# MainBoard.net
KiCad netlist of a schematic drawn in Altium Designer
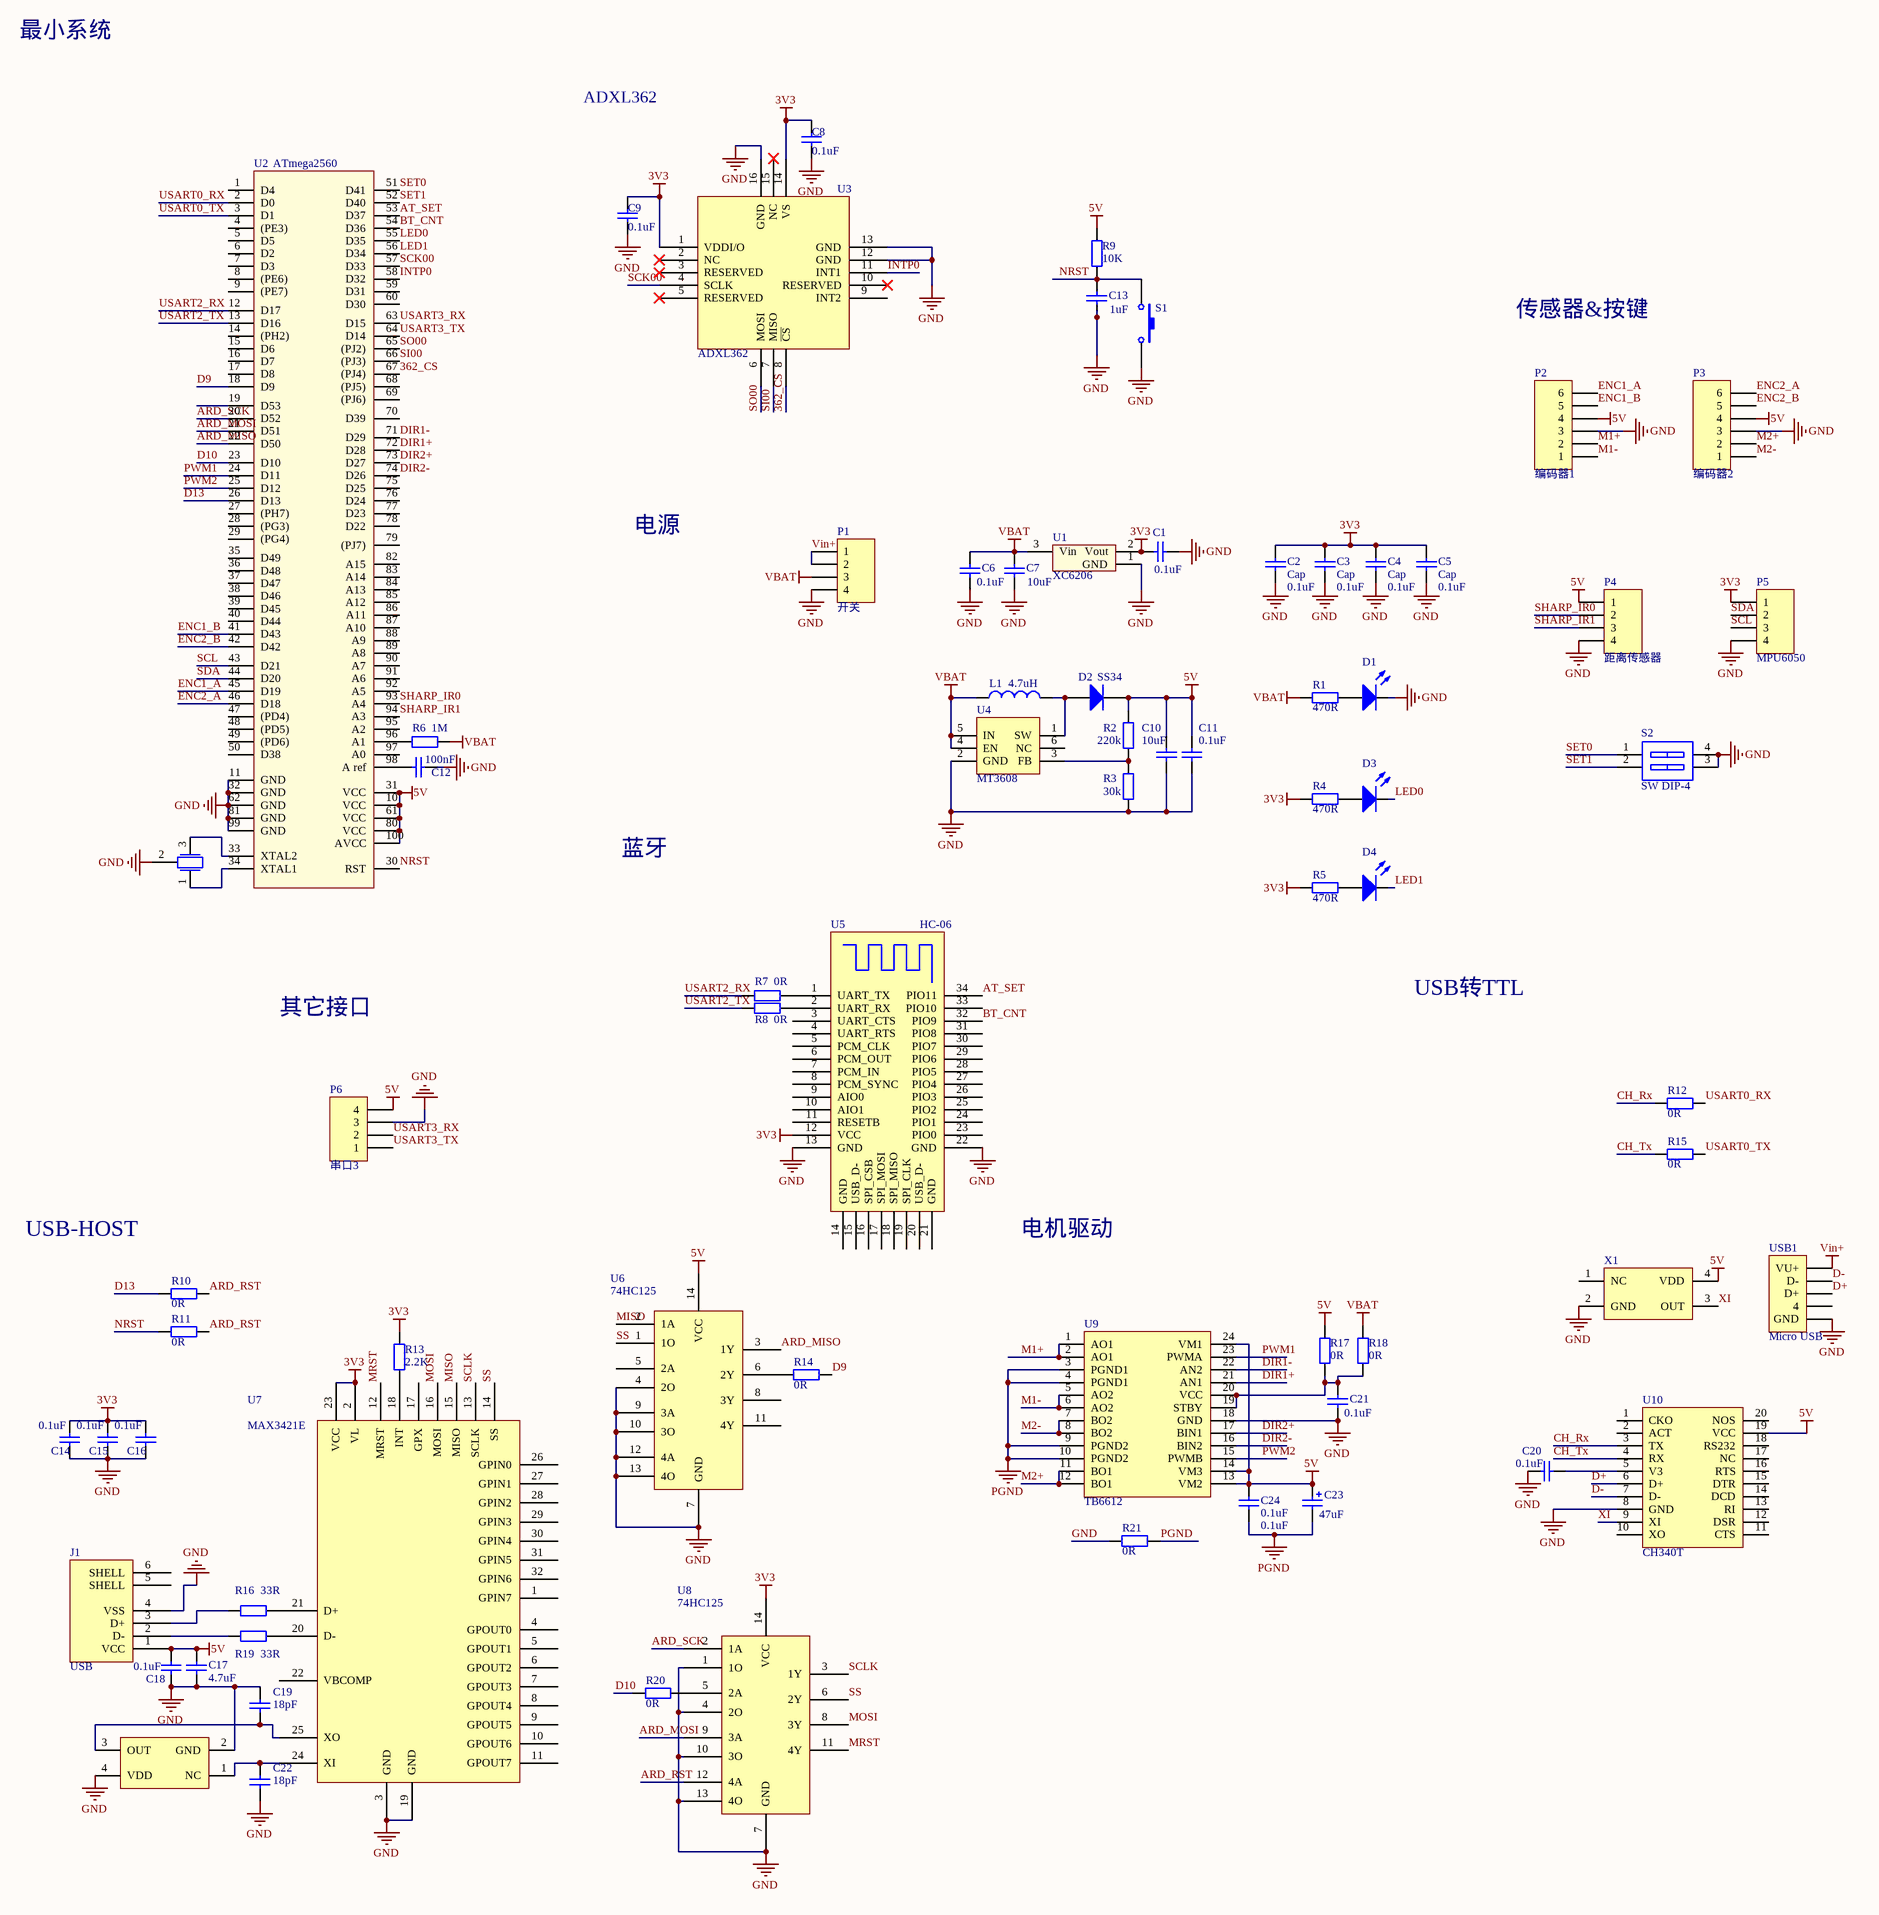
[diagram p0: MainBoard.SchDoc]

(export (version "E")
  (design (tool "Eeschema 10.0.6"))
  (components
    (comp (ref "*1") (value "5032晶振") (footprint "5032晶振") (libsource (lib "") (part "5032晶振_1")))
    (comp (ref "C1")
      (value "0.1uF")
      (footprint "0402C")
      (description "Capacitor")
      (fields (field (name "Comment") "Cap") (field (name "PUBLISHER") "Altium Limited"))
      (libsource (lib "myLib") (part "Cap"))
    )
    (comp (ref "C2")
      (value "Cap")
      (footprint "0402C")
      (description "Capacitor")
      (fields (field (name "ALTIUM_VALUE") "0.1uF") (field (name "PUBLISHER") "Altium Limited"))
      (libsource (lib "myLib") (part "Cap"))
    )
    (comp (ref "C3")
      (value "Cap")
      (footprint "0402C")
      (description "Capacitor")
      (fields (field (name "ALTIUM_VALUE") "0.1uF") (field (name "PUBLISHER") "Altium Limited"))
      (libsource (lib "myLib") (part "Cap"))
    )
    (comp (ref "C4")
      (value "Cap")
      (footprint "0402C")
      (description "Capacitor")
      (fields (field (name "ALTIUM_VALUE") "0.1uF") (field (name "PUBLISHER") "Altium Limited"))
      (libsource (lib "myLib") (part "Cap"))
    )
    (comp (ref "C5")
      (value "Cap")
      (footprint "0402C")
      (description "Capacitor")
      (fields (field (name "ALTIUM_VALUE") "0.1uF") (field (name "PUBLISHER") "Altium Limited"))
      (libsource (lib "myLib") (part "Cap"))
    )
    (comp (ref "C6")
      (value "0.1uF")
      (footprint "0402C")
      (description "Capacitor")
      (fields (field (name "Comment") "Cap") (field (name "PUBLISHER") "Altium Limited"))
      (libsource (lib "myLib") (part "Cap"))
    )
    (comp (ref "C7")
      (value "10uF")
      (footprint "0603_M")
      (description "Capacitor")
      (fields (field (name "Comment") "Cap") (field (name "PUBLISHER") "Altium Limited"))
      (libsource (lib "myLib") (part "Cap"))
    )
    (comp (ref "C8")
      (value "0.1uF")
      (footprint "0805")
      (description "Capacitor 0805")
      (fields (field (name "PUBLISHER") "Altium Limited"))
      (libsource (lib "MAE1_Integrated_Library_Ver1.05_20131010") (part "Cap2"))
    )
    (comp (ref "C9")
      (value "0.1uF")
      (footprint "0805")
      (description "Capacitor 0805")
      (fields (field (name "PUBLISHER") "Altium Limited"))
      (libsource (lib "MAE1_Integrated_Library_Ver1.05_20131010") (part "Cap2"))
    )
    (comp (ref "C10")
      (value "10uF")
      (footprint "0603_M")
      (description "Capacitor 100nF (104) ±10% 25V 0603")
      (fields (field (name "PUBLISHER") "Altium Limited"))
      (libsource (lib "Miscellaneous Devices") (part "Cap"))
    )
    (comp (ref "C11")
      (value "0.1uF")
      (footprint "0402C")
      (description "Capacitor (Semiconductor SIM Model)")
      (fields (field (name "PUBLISHER") "Altium Limited"))
      (libsource (lib "Miscellaneous Devices") (part "Cap Semi"))
    )
    (comp (ref "C12")
      (value "100nF")
      (footprint "0402")
      (description "Capacitor")
      (fields (field (name "Comment") "电容_0402") (field (name "PUBLISHER") "Altium Limited"))
      (libsource (lib "myLib") (part "电容_0402"))
    )
    (comp (ref "C13")
      (value "1uF")
      (footprint "0402C")
      (description "Capacitor")
      (fields (field (name "Comment") "Cap") (field (name "PUBLISHER") "Altium Limited"))
      (libsource (lib "myLib") (part "Cap"))
    )
    (comp (ref "C14")
      (value "0.1uF")
      (footprint "0402")
      (description "Capacitor")
      (fields (field (name "Comment") "电容_0603") (field (name "PUBLISHER") "Altium Limited"))
      (libsource (lib "myLib") (part "电容_0603"))
    )
    (comp (ref "C15")
      (value "0.1uF")
      (footprint "0402")
      (description "Capacitor")
      (fields (field (name "Comment") "电容_0603") (field (name "PUBLISHER") "Altium Limited"))
      (libsource (lib "myLib") (part "电容_0603"))
    )
    (comp (ref "C16")
      (value "0.1uF")
      (footprint "0402")
      (description "Capacitor")
      (fields (field (name "Comment") "电容_0603") (field (name "PUBLISHER") "Altium Limited"))
      (libsource (lib "myLib") (part "电容_0603"))
    )
    (comp (ref "C17")
      (value "4.7uF")
      (footprint "C1206")
      (description "Capacitor (Semiconductor SIM Model)")
      (fields (field (name "Comment") "Cap Semi") (field (name "PUBLISHER") "Altium Limited"))
      (libsource (lib "Miscellaneous Devices") (part "Cap Semi"))
    )
    (comp (ref "C18")
      (value "0.1uF")
      (footprint "0402")
      (description "Capacitor")
      (fields (field (name "Comment") "电容_0603") (field (name "PUBLISHER") "Altium Limited"))
      (libsource (lib "myLib") (part "电容_0603"))
    )
    (comp (ref "C19")
      (value "18pF")
      (footprint "0402")
      (description "Capacitor")
      (fields (field (name "Comment") "电容_0603") (field (name "PUBLISHER") "Altium Limited"))
      (libsource (lib "myLib") (part "电容_0603"))
    )
    (comp (ref "C20")
      (value "0.1uF")
      (footprint "0402C")
      (description "Capacitor")
      (fields (field (name "Comment") "Cap") (field (name "PUBLISHER") "Altium Limited"))
      (libsource (lib "myLib") (part "Cap"))
    )
    (comp (ref "C21")
      (value "0.1uF")
      (footprint "0603_M")
      (description "Capacitor")
      (fields (field (name "Comment") "value") (field (name "PUBLISHER") "Altium Limited"))
      (libsource (lib "Miscellaneous Devices") (part "Cap"))
    )
    (comp (ref "C22")
      (value "18pF")
      (footprint "0402")
      (description "Capacitor")
      (fields (field (name "Comment") "电容_0603") (field (name "PUBLISHER") "Altium Limited"))
      (libsource (lib "myLib") (part "电容_0603"))
    )
    (comp (ref "C23")
      (value "47uF")
      (footprint "CAP 6X7mm 贴片电解")
      (description "Polarized Capacitor (Radial)")
      (fields (field (name "Comment") "钽电容6x7mm") (field (name "PUBLISHER") "Altium Limited"))
      (libsource (lib "myLib") (part "钽电容6x7mm"))
    )
    (comp (ref "C24")
      (value "0.1uF")
      (footprint "0603_M")
      (description "Capacitor")
      (fields (field (name "ALTIUM_VALUE") "0.1uF") (field (name "PUBLISHER") "Altium Limited"))
      (libsource (lib "Miscellaneous Devices") (part "Cap"))
    )
    (comp (ref "D1")
      (value "LED")
      (footprint "0603_M")
      (description "Typical INFRARED GaAs LED")
      (fields (field (name "PUBLISHER") "Altium Limited"))
      (libsource (lib "myLib") (part "LED0"))
    )
    (comp (ref "D2")
      (value "SS34")
      (footprint "DO-214")
      (description "Diode  SS34 DO214-AC")
      (fields (field (name "PUBLISHER") "Altium Limited"))
      (libsource (lib "Miscellaneous Devices") (part "Diode"))
    )
    (comp (ref "D3")
      (value "LED")
      (footprint "0603_M")
      (description "Typical INFRARED GaAs LED")
      (fields (field (name "PUBLISHER") "Altium Limited"))
      (libsource (lib "myLib") (part "LED0"))
    )
    (comp (ref "D4")
      (value "LED")
      (footprint "0603_M")
      (description "Typical INFRARED GaAs LED")
      (fields (field (name "PUBLISHER") "Altium Limited"))
      (libsource (lib "myLib") (part "LED0"))
    )
    (comp (ref "J1")
      (value "USB")
      (footprint "USB_A1")
      (description "USB接口")
      (libsource (lib "myLib") (part "USB"))
    )
    (comp (ref "L1")
      (value "4.7uH")
      (footprint "贴片电感CD32")
      (description "Inductor, 6.8uH, 4.5A, 1054 SMD")
      (fields (field (name "PUBLISHER") "Altium Limited"))
      (libsource (lib "myLib") (part "贴片电感"))
    )
    (comp (ref "P1")
      (value "开关")
      (footprint "HDR1X4")
      (description "Header, 4-Pin")
      (fields (field (name "PUBLISHER") "Altium Limited"))
      (libsource (lib "Miscellaneous Connectors") (part "Header 4"))
    )
    (comp (ref "P2")
      (value "编码器1")
      (footprint "接插件6x1.25mm")
      (libsource (lib "myLib") (part "接插件6x1.25mm_1"))
    )
    (comp (ref "P3")
      (value "编码器2")
      (footprint "接插件6x1.25mm")
      (libsource (lib "myLib") (part "接插件6x1.25mm_1"))
    )
    (comp (ref "P4")
      (value "距离传感器")
      (footprint "接插件4x1.25mm")
      (description "Header, 4-Pin")
      (fields (field (name "PUBLISHER") "Altium Limited"))
      (libsource (lib "Miscellaneous Connectors") (part "MHDR1X4"))
    )
    (comp (ref "P5") (value "MPU6050") (footprint "接插件4x1.25mm") (libsource (lib "") (part "接插件4x1.25mm_1")))
    (comp (ref "P6") (value "串口3") (footprint "接插件4x1.25mm") (libsource (lib "myLib") (part "接插件4x1.25mm")))
    (comp (ref "R1")
      (value "470R")
      (footprint "0402C")
      (description "Resistor")
      (fields (field (name "Comment") "电阻_0402") (field (name "PUBLISHER") "Altium Limited"))
      (libsource (lib "myLib") (part "电阻_0402"))
    )
    (comp (ref "R2")
      (value "220k")
      (footprint "0603_M")
      (description "Resistor, 22R 1% 0603 (1608)")
      (fields (field (name "PUBLISHER") "Altium Limited"))
      (libsource (lib "Miscellaneous Devices") (part "Res2"))
    )
    (comp (ref "R3")
      (value "30k")
      (footprint "0603_M")
      (description "Resistor, 22R 1% 0603 (1608)")
      (fields (field (name "PUBLISHER") "Altium Limited"))
      (libsource (lib "Miscellaneous Devices") (part "Res2"))
    )
    (comp (ref "R4")
      (value "470R")
      (footprint "0402C")
      (description "Resistor")
      (fields (field (name "Comment") "电阻_0402") (field (name "PUBLISHER") "Altium Limited"))
      (libsource (lib "myLib") (part "电阻_0402"))
    )
    (comp (ref "R5")
      (value "470R")
      (footprint "0402C")
      (description "Resistor")
      (fields (field (name "Comment") "电阻_0402") (field (name "PUBLISHER") "Altium Limited"))
      (libsource (lib "myLib") (part "电阻_0402"))
    )
    (comp (ref "R6")
      (value "1M")
      (footprint "0402C")
      (description "Resistor")
      (fields (field (name "Comment") "电阻_0402") (field (name "PUBLISHER") "Altium Limited"))
      (libsource (lib "myLib") (part "电阻_0402"))
    )
    (comp (ref "R7")
      (value "0R")
      (footprint "0R电阻")
      (description "Resistor")
      (fields (field (name "Comment") "0R电阻") (field (name "PUBLISHER") "Altium Limited"))
      (libsource (lib "myLib") (part "0R电阻"))
    )
    (comp (ref "R8")
      (value "0R")
      (footprint "0R电阻")
      (description "Resistor")
      (fields (field (name "Comment") "0R电阻") (field (name "PUBLISHER") "Altium Limited"))
      (libsource (lib "myLib") (part "0R电阻"))
    )
    (comp (ref "R9")
      (value "10K")
      (footprint "0402C")
      (description "Resistor")
      (fields (field (name "Comment") "Res2") (field (name "PUBLISHER") "Altium Limited"))
      (libsource (lib "myLib") (part "Res2"))
    )
    (comp (ref "R10")
      (value "0R")
      (footprint "0R电阻")
      (description "Resistor")
      (fields (field (name "Comment") "0R电阻") (field (name "PUBLISHER") "Altium Limited"))
      (libsource (lib "myLib") (part "0R电阻"))
    )
    (comp (ref "R11")
      (value "0R")
      (footprint "0R电阻")
      (description "Resistor")
      (fields (field (name "Comment") "0R电阻") (field (name "PUBLISHER") "Altium Limited"))
      (libsource (lib "myLib") (part "0R电阻"))
    )
    (comp (ref "R12")
      (value "0R")
      (footprint "0R电阻")
      (description "Resistor")
      (fields (field (name "Comment") "0R电阻") (field (name "PUBLISHER") "Altium Limited"))
      (libsource (lib "myLib") (part "0R电阻"))
    )
    (comp (ref "R13")
      (value "2.2K")
      (footprint "0603_M")
      (description "Resistor")
      (fields (field (name "Comment") "电阻_0603") (field (name "PUBLISHER") "Altium Limited"))
      (libsource (lib "") (part "电阻_0603_1"))
    )
    (comp (ref "R14")
      (value "0R")
      (footprint "0R电阻")
      (description "Resistor")
      (fields (field (name "Comment") "0R电阻") (field (name "PUBLISHER") "Altium Limited"))
      (libsource (lib "myLib") (part "0R电阻"))
    )
    (comp (ref "R15")
      (value "0R")
      (footprint "0R电阻")
      (description "Resistor")
      (fields (field (name "Comment") "0R电阻") (field (name "PUBLISHER") "Altium Limited"))
      (libsource (lib "myLib") (part "0R电阻"))
    )
    (comp (ref "R16")
      (value "33R")
      (footprint "0603_M")
      (description "Resistor")
      (fields (field (name "Comment") "电阻_0603") (field (name "PUBLISHER") "Altium Limited"))
      (libsource (lib "myLib") (part "电阻_0603"))
    )
    (comp (ref "R17")
      (value "0R")
      (footprint "0R电阻")
      (description "Resistor")
      (fields (field (name "Comment") "0R电阻") (field (name "PUBLISHER") "Altium Limited"))
      (libsource (lib "") (part "0R电阻_1"))
    )
    (comp (ref "R18")
      (value "0R")
      (footprint "0R电阻")
      (description "Resistor")
      (fields (field (name "Comment") "0R电阻") (field (name "PUBLISHER") "Altium Limited"))
      (libsource (lib "") (part "0R电阻_1"))
    )
    (comp (ref "R19")
      (value "33R")
      (footprint "0603_M")
      (description "Resistor")
      (fields (field (name "Comment") "电阻_0603") (field (name "PUBLISHER") "Altium Limited"))
      (libsource (lib "myLib") (part "电阻_0603"))
    )
    (comp (ref "R20")
      (value "0R")
      (footprint "0R电阻")
      (description "Resistor")
      (fields (field (name "Comment") "0R电阻") (field (name "PUBLISHER") "Altium Limited"))
      (libsource (lib "myLib") (part "0R电阻"))
    )
    (comp (ref "R21")
      (value "0R")
      (footprint "0R电阻")
      (description "Resistor")
      (fields (field (name "Comment") "0R电阻") (field (name "PUBLISHER") "Altium Limited"))
      (libsource (lib "myLib") (part "0R电阻"))
    )
    (comp (ref "S1")
      (value "SW-PB")
      (footprint "SW_PB2_A1")
      (description "微动开关")
      (fields (field (name "PUBLISHER") "Altium Limited"))
      (libsource (lib "myLib") (part "SW-PB"))
    )
    (comp (ref "S2")
      (value "SW DIP-4")
      (footprint "SW8_4BIT")
      (description "编码开关")
      (fields (field (name "PUBLISHER") "Altium Limited"))
      (libsource (lib "myLib") (part "SW DIP-4"))
    )
    (comp (ref "U1") (value "XC6206") (footprint "SOT-23") (libsource (lib "myLib") (part "XC6206")))
    (comp (ref "U2") (value "ATmega2560") (footprint "QFP-100") (libsource (lib "myLib") (part "ATmega2560")))
    (comp (ref "U3")
      (value "ADXL362")
      (footprint "脚部传感器1:MAX21100")
      (libsource (lib "pedometer") (part "ADXL362"))
    )
    (comp (ref "U4")
      (value "MT3608")
      (footprint "SOT23-6")
      (description "升压IC")
      (libsource (lib "my元器件原理图") (part "MT3608"))
    )
    (comp (ref "U5")
      (value "HC-06")
      (footprint "HM_01_02_09_10")
      (description "HM bluetooth module HM-01,HM-02,HM-09")
      (libsource (lib "HMSoft") (part "HM01_02_09_1"))
    )
    (comp (ref "U6") (value "74HC125") (footprint "SOIC-14") (libsource (lib "myLib") (part "74HC125")))
    (comp (ref "U7") (value "MAX3421E") (footprint "TQFP-32") (libsource (lib "myLib") (part "MAX3421E")))
    (comp (ref "U8") (value "74HC125") (footprint "SOIC-14") (libsource (lib "myLib") (part "74HC125")))
    (comp (ref "U9") (value "TB6612") (footprint "SOP65P760-24") (libsource (lib "Mylib") (part "TB6612")))
    (comp (ref "U10") (value "CH340T") (footprint "SSOP20") (libsource (lib "myLib") (part "CH340T")))
    (comp (ref "USB1")
      (value "Micro USB")
      (footprint "USB MICRO")
      (description "USB")
      (fields (field (name "PUBLISHER") "Altium Limited"))
      (libsource (lib "myLib") (part "Micro USB"))
    )
    (comp (ref "X1") (value "5032晶振") (footprint "5032晶振") (libsource (lib "myLib") (part "5032晶振")))
    (comp (ref "Y1")
      (value "XTAL-3PIN")
      (footprint "X-CPX20")
      (description "贴片晶振")
      (libsource (lib "myLib") (part "XTAL-3PIN"))
    )
  )
  (nets
    (net (code "1") (name "/362_CS") (class "Default")
      (node (ref "U2") (pin "67") (pinfunction "(PJ4)_67") (pintype "passive"))
      (node (ref "U3") (pin "8") (pinfunction "~{CS}_8") (pintype "passive"))
    )
    (net (code "2") (name "/ARD_MISO") (class "Default")
      (node (ref "U2") (pin "22") (pinfunction "D50_22") (pintype "passive"))
      (node (ref "U6") (pin "3") (pinfunction "1Y_3") (pintype "passive"))
    )
    (net (code "3") (name "/ARD_MOSI") (class "Default")
      (node (ref "U2") (pin "21") (pinfunction "D51_21") (pintype "passive"))
      (node (ref "U8") (pin "9") (pinfunction "3A_9") (pintype "passive"))
    )
    (net (code "4") (name "/ARD_RST") (class "Default")
      (node (ref "R10") (pin "2") (pinfunction "2_2") (pintype "passive"))
      (node (ref "R11") (pin "2") (pinfunction "2_2") (pintype "passive"))
      (node (ref "U8") (pin "12") (pinfunction "4A_12") (pintype "passive"))
    )
    (net (code "5") (name "/ARD_SCK") (class "Default")
      (node (ref "U2") (pin "20") (pinfunction "D52_20") (pintype "passive"))
      (node (ref "U8") (pin "2") (pinfunction "1A_2") (pintype "passive"))
    )
    (net (code "6") (name "/AT_SET") (class "Default")
      (node (ref "U2") (pin "53") (pinfunction "D37_53") (pintype "passive"))
      (node (ref "U5") (pin "34") (pinfunction "PIO11_34") (pintype "passive"))
    )
    (net (code "7") (name "/BT_CNT") (class "Default")
      (node (ref "U2") (pin "54") (pinfunction "D36_54") (pintype "passive"))
      (node (ref "U5") (pin "32") (pinfunction "PIO9_32") (pintype "passive"))
    )
    (net (code "8") (name "/CH_Rx") (class "Default")
      (node (ref "R12") (pin "1") (pinfunction "1_1") (pintype "passive"))
      (node (ref "U10") (pin "3") (pinfunction "TX_3") (pintype "passive"))
    )
    (net (code "9") (name "/CH_Tx") (class "Default")
      (node (ref "R15") (pin "1") (pinfunction "1_1") (pintype "passive"))
      (node (ref "U10") (pin "4") (pinfunction "RX_4") (pintype "passive"))
    )
    (net (code "10") (name "/D+") (class "Default")
      (node (ref "U10") (pin "6") (pinfunction "D+_6") (pintype "passive"))
      (node (ref "USB1") (pin "3") (pinfunction "D+_3") (pintype "passive"))
    )
    (net (code "11") (name "/D-") (class "Default")
      (node (ref "U10") (pin "7") (pinfunction "D-_7") (pintype "passive"))
      (node (ref "USB1") (pin "2") (pinfunction "D-_2") (pintype "passive"))
    )
    (net (code "12") (name "/D9") (class "Default")
      (node (ref "R14") (pin "2") (pinfunction "2_2") (pintype "passive"))
      (node (ref "U2") (pin "18") (pinfunction "D9_18") (pintype "passive"))
    )
    (net (code "13") (name "/D10") (class "Default")
      (node (ref "R20") (pin "1") (pinfunction "1_1") (pintype "passive"))
      (node (ref "U2") (pin "23") (pinfunction "D10_23") (pintype "passive"))
    )
    (net (code "14") (name "/D13") (class "Default")
      (node (ref "R10") (pin "1") (pinfunction "1_1") (pintype "passive"))
      (node (ref "U2") (pin "26") (pinfunction "D13_26") (pintype "passive"))
    )
    (net (code "15") (name "/DIR1+") (class "Default")
      (node (ref "U2") (pin "72") (pinfunction "D28_72") (pintype "passive"))
      (node (ref "U9") (pin "21") (pinfunction "AN1_21") (pintype "passive"))
    )
    (net (code "16") (name "/DIR1-") (class "Default")
      (node (ref "U2") (pin "71") (pinfunction "D29_71") (pintype "passive"))
      (node (ref "U9") (pin "22") (pinfunction "AN2_22") (pintype "passive"))
    )
    (net (code "17") (name "/DIR2+") (class "Default")
      (node (ref "U2") (pin "73") (pinfunction "D27_73") (pintype "passive"))
      (node (ref "U9") (pin "17") (pinfunction "BIN1_17") (pintype "passive"))
    )
    (net (code "18") (name "/DIR2-") (class "Default")
      (node (ref "U2") (pin "74") (pinfunction "D26_74") (pintype "passive"))
      (node (ref "U9") (pin "16") (pinfunction "BIN2_16") (pintype "passive"))
    )
    (net (code "19") (name "/ENC1_A") (class "Default")
      (node (ref "P2") (pin "6") (pinfunction "6_6") (pintype "passive"))
      (node (ref "U2") (pin "45") (pinfunction "D19_45") (pintype "passive"))
    )
    (net (code "20") (name "/ENC1_B") (class "Default")
      (node (ref "P2") (pin "5") (pinfunction "5_5") (pintype "passive"))
      (node (ref "U2") (pin "41") (pinfunction "D43_41") (pintype "passive"))
    )
    (net (code "21") (name "/ENC2_A") (class "Default")
      (node (ref "P3") (pin "6") (pinfunction "6_6") (pintype "passive"))
      (node (ref "U2") (pin "46") (pinfunction "D18_46") (pintype "passive"))
    )
    (net (code "22") (name "/ENC2_B") (class "Default")
      (node (ref "P3") (pin "5") (pinfunction "5_5") (pintype "passive"))
      (node (ref "U2") (pin "42") (pinfunction "D42_42") (pintype "passive"))
    )
    (net (code "23") (name "/INTP0") (class "Default")
      (node (ref "U2") (pin "58") (pinfunction "D32_58") (pintype "passive"))
      (node (ref "U3") (pin "11") (pinfunction "INT1_11") (pintype "passive"))
    )
    (net (code "24") (name "/LED0") (class "Default")
      (node (ref "D3") (pin "2") (pinfunction "K_2") (pintype "passive"))
      (node (ref "U2") (pin "55") (pinfunction "D35_55") (pintype "passive"))
    )
    (net (code "25") (name "/LED1") (class "Default")
      (node (ref "D4") (pin "2") (pinfunction "K_2") (pintype "passive"))
      (node (ref "U2") (pin "56") (pinfunction "D34_56") (pintype "passive"))
    )
    (net (code "26") (name "/M1+") (class "Default")
      (node (ref "P2") (pin "2") (pinfunction "2_2") (pintype "passive"))
      (node (ref "U9") (pin "1") (pinfunction "AO1_1") (pintype "passive"))
      (node (ref "U9") (pin "2") (pinfunction "AO1_2") (pintype "passive"))
    )
    (net (code "27") (name "/M1-") (class "Default")
      (node (ref "P2") (pin "1") (pinfunction "1_1") (pintype "passive"))
      (node (ref "U9") (pin "5") (pinfunction "AO2_5") (pintype "passive"))
      (node (ref "U9") (pin "6") (pinfunction "AO2_6") (pintype "passive"))
    )
    (net (code "28") (name "/M2+") (class "Default")
      (node (ref "P3") (pin "2") (pinfunction "2_2") (pintype "passive"))
      (node (ref "U9") (pin "11") (pinfunction "BO1_11") (pintype "passive"))
      (node (ref "U9") (pin "12") (pinfunction "BO1_12") (pintype "passive"))
    )
    (net (code "29") (name "/M2-") (class "Default")
      (node (ref "P3") (pin "1") (pinfunction "1_1") (pintype "passive"))
      (node (ref "U9") (pin "7") (pinfunction "BO2_7") (pintype "passive"))
      (node (ref "U9") (pin "8") (pinfunction "BO2_8") (pintype "passive"))
    )
    (net (code "30") (name "/MISO") (class "Default")
      (node (ref "U6") (pin "2") (pinfunction "1A_2") (pintype "passive"))
      (node (ref "U7") (pin "15") (pinfunction "MISO_15") (pintype "passive"))
    )
    (net (code "31") (name "/MOSI") (class "Default")
      (node (ref "U7") (pin "16") (pinfunction "MOSI_16") (pintype "passive"))
      (node (ref "U8") (pin "8") (pinfunction "3Y_8") (pintype "passive"))
    )
    (net (code "32") (name "/MRST") (class "Default")
      (node (ref "U7") (pin "12") (pinfunction "MRST_12") (pintype "passive"))
      (node (ref "U8") (pin "11") (pinfunction "4Y_11") (pintype "passive"))
    )
    (net (code "33") (name "/NRST") (class "Default")
      (node (ref "C13") (pin "2") (pinfunction "2_2") (pintype "passive"))
      (node (ref "R11") (pin "1") (pinfunction "1_1") (pintype "passive"))
      (node (ref "R9") (pin "1") (pinfunction "1_1") (pintype "passive"))
      (node (ref "S1") (pin "1") (pinfunction "1_1") (pintype "passive"))
      (node (ref "U2") (pin "30") (pinfunction "RST_30") (pintype "passive"))
    )
    (net (code "34") (name "/PWM1") (class "Default")
      (node (ref "U2") (pin "24") (pinfunction "D11_24") (pintype "passive"))
      (node (ref "U9") (pin "23") (pinfunction "PWMA_23") (pintype "passive"))
    )
    (net (code "35") (name "/PWM2") (class "Default")
      (node (ref "U2") (pin "25") (pinfunction "D12_25") (pintype "passive"))
      (node (ref "U9") (pin "15") (pinfunction "PWMB_15") (pintype "passive"))
    )
    (net (code "36") (name "/SCK00") (class "Default")
      (node (ref "U2") (pin "57") (pinfunction "D33_57") (pintype "passive"))
      (node (ref "U3") (pin "4") (pinfunction "SCLK_4") (pintype "passive"))
    )
    (net (code "37") (name "/SCL") (class "Default")
      (node (ref "P5") (pin "3") (pinfunction "3_3") (pintype "passive"))
      (node (ref "U2") (pin "43") (pinfunction "D21_43") (pintype "passive"))
    )
    (net (code "38") (name "/SCLK") (class "Default")
      (node (ref "U7") (pin "13") (pinfunction "SCLK_13") (pintype "passive"))
      (node (ref "U8") (pin "3") (pinfunction "1Y_3") (pintype "passive"))
    )
    (net (code "39") (name "/SDA") (class "Default")
      (node (ref "P5") (pin "2") (pinfunction "2_2") (pintype "passive"))
      (node (ref "U2") (pin "44") (pinfunction "D20_44") (pintype "passive"))
    )
    (net (code "40") (name "/SET0") (class "Default")
      (node (ref "S2") (pin "1") (pinfunction "A1_1") (pintype "passive"))
      (node (ref "U2") (pin "51") (pinfunction "D41_51") (pintype "passive"))
    )
    (net (code "41") (name "/SET1") (class "Default")
      (node (ref "S2") (pin "2") (pinfunction "A2_2") (pintype "passive"))
      (node (ref "U2") (pin "52") (pinfunction "D40_52") (pintype "passive"))
    )
    (net (code "42") (name "/SHARP_IR0") (class "Default")
      (node (ref "P4") (pin "2") (pinfunction "2_2") (pintype "passive"))
      (node (ref "U2") (pin "93") (pinfunction "A4_93") (pintype "passive"))
    )
    (net (code "43") (name "/SHARP_IR1") (class "Default")
      (node (ref "P4") (pin "3") (pinfunction "3_3") (pintype "passive"))
      (node (ref "U2") (pin "94") (pinfunction "A3_94") (pintype "passive"))
    )
    (net (code "44") (name "/SI00") (class "Default")
      (node (ref "U2") (pin "66") (pinfunction "(PJ3)_66") (pintype "passive"))
      (node (ref "U3") (pin "7") (pinfunction "MISO_7") (pintype "passive"))
    )
    (net (code "45") (name "/SO00") (class "Default")
      (node (ref "U2") (pin "65") (pinfunction "(PJ2)_65") (pintype "passive"))
      (node (ref "U3") (pin "6") (pinfunction "MOSI_6") (pintype "passive"))
    )
    (net (code "46") (name "/SS") (class "Default")
      (node (ref "U6") (pin "1") (pinfunction "1O_1") (pintype "passive"))
      (node (ref "U7") (pin "14") (pinfunction "SS_14") (pintype "passive"))
      (node (ref "U8") (pin "6") (pinfunction "2Y_6") (pintype "passive"))
    )
    (net (code "47") (name "/USART0_RX") (class "Default")
      (node (ref "R12") (pin "2") (pinfunction "2_2") (pintype "passive"))
      (node (ref "U2") (pin "2") (pinfunction "D0_2") (pintype "passive"))
    )
    (net (code "48") (name "/USART0_TX") (class "Default")
      (node (ref "R15") (pin "2") (pinfunction "2_2") (pintype "passive"))
      (node (ref "U2") (pin "3") (pinfunction "D1_3") (pintype "passive"))
    )
    (net (code "49") (name "/USART2_RX") (class "Default")
      (node (ref "R7") (pin "1") (pinfunction "1_1") (pintype "passive"))
      (node (ref "U2") (pin "12") (pinfunction "D17_12") (pintype "passive"))
    )
    (net (code "50") (name "/USART2_TX") (class "Default")
      (node (ref "R8") (pin "1") (pinfunction "1_1") (pintype "passive"))
      (node (ref "U2") (pin "13") (pinfunction "D16_13") (pintype "passive"))
    )
    (net (code "51") (name "/USART3_RX") (class "Default")
      (node (ref "P6") (pin "2") (pinfunction "2_2") (pintype "passive"))
      (node (ref "U2") (pin "63") (pinfunction "D15_63") (pintype "passive"))
    )
    (net (code "52") (name "/USART3_TX") (class "Default")
      (node (ref "P6") (pin "1") (pinfunction "1_1") (pintype "passive"))
      (node (ref "U2") (pin "64") (pinfunction "D14_64") (pintype "passive"))
    )
    (net (code "53") (name "/XI") (class "Default")
      (node (ref "U10") (pin "9") (pinfunction "XI_9") (pintype "passive"))
      (node (ref "X1") (pin "3") (pinfunction "OUT_3") (pintype "passive"))
    )
    (net (code "54") (name "3V3") (class "Default")
      (node (ref "C1") (pin "1") (pinfunction "1_1") (pintype "passive"))
      (node (ref "C14") (pin "1") (pinfunction "1_1") (pintype "passive"))
      (node (ref "C15") (pin "1") (pinfunction "1_1") (pintype "passive"))
      (node (ref "C16") (pin "1") (pinfunction "1_1") (pintype "passive"))
      (node (ref "C2") (pin "2") (pinfunction "2_2") (pintype "passive"))
      (node (ref "C3") (pin "2") (pinfunction "2_2") (pintype "passive"))
      (node (ref "C4") (pin "2") (pinfunction "2_2") (pintype "passive"))
      (node (ref "C5") (pin "2") (pinfunction "2_2") (pintype "passive"))
      (node (ref "C8") (pin "2") (pinfunction "2_2") (pintype "passive"))
      (node (ref "C9") (pin "2") (pinfunction "2_2") (pintype "passive"))
      (node (ref "P5") (pin "1") (pinfunction "1_1") (pintype "passive"))
      (node (ref "R13") (pin "2") (pinfunction "2_2") (pintype "passive"))
      (node (ref "R4") (pin "1") (pinfunction "1_1") (pintype "passive"))
      (node (ref "R5") (pin "1") (pinfunction "1_1") (pintype "passive"))
      (node (ref "U1") (pin "2") (pinfunction "Vout_2") (pintype "passive"))
      (node (ref "U3") (pin "1") (pinfunction "VDDI/O_1") (pintype "passive"))
      (node (ref "U3") (pin "14") (pinfunction "VS_14") (pintype "passive"))
      (node (ref "U5") (pin "12") (pinfunction "VCC_12") (pintype "passive"))
      (node (ref "U7") (pin "2") (pinfunction "VL_2") (pintype "passive"))
      (node (ref "U7") (pin "23") (pinfunction "VCC_23") (pintype "passive"))
      (node (ref "U8") (pin "14") (pinfunction "VCC_14") (pintype "passive"))
    )
    (net (code "55") (name "5V") (class "Default")
      (node (ref "C10") (pin "2") (pinfunction "2_2") (pintype "passive"))
      (node (ref "C11") (pin "2") (pinfunction "2_2") (pintype "passive"))
      (node (ref "C17") (pin "2") (pinfunction "2_2") (pintype "passive"))
      (node (ref "C18") (pin "1") (pinfunction "1_1") (pintype "passive"))
      (node (ref "C23") (pin "1") (pinfunction "1_1") (pintype "passive"))
      (node (ref "C24") (pin "2") (pinfunction "2_2") (pintype "passive"))
      (node (ref "D2") (pin "2") (pinfunction "K_2") (pintype "passive"))
      (node (ref "J1") (pin "1") (pinfunction "VCC_1") (pintype "passive"))
      (node (ref "P2") (pin "4") (pinfunction "4_4") (pintype "passive"))
      (node (ref "P3") (pin "4") (pinfunction "4_4") (pintype "passive"))
      (node (ref "P4") (pin "1") (pinfunction "1_1") (pintype "passive"))
      (node (ref "P6") (pin "4") (pinfunction "4_4") (pintype "passive"))
      (node (ref "R17") (pin "2") (pinfunction "2_2") (pintype "passive"))
      (node (ref "R2") (pin "1") (pinfunction "1_1") (pintype "passive"))
      (node (ref "R9") (pin "2") (pinfunction "2_2") (pintype "passive"))
      (node (ref "U10") (pin "19") (pinfunction "VCC_19") (pintype "passive"))
      (node (ref "U2") (pin "10") (pinfunction "VCC_10") (pintype "passive"))
      (node (ref "U2") (pin "100") (pinfunction "AVCC_100") (pintype "passive"))
      (node (ref "U2") (pin "31") (pinfunction "VCC_31") (pintype "passive"))
      (node (ref "U2") (pin "61") (pinfunction "VCC_61") (pintype "passive"))
      (node (ref "U2") (pin "80") (pinfunction "VCC_80") (pintype "passive"))
      (node (ref "U6") (pin "14") (pinfunction "VCC_14") (pintype "passive"))
      (node (ref "U9") (pin "13") (pinfunction "VM2_13") (pintype "passive"))
      (node (ref "U9") (pin "14") (pinfunction "VM3_14") (pintype "passive"))
      (node (ref "U9") (pin "24") (pinfunction "VM1_24") (pintype "passive"))
      (node (ref "X1") (pin "4") (pinfunction "VDD_4") (pintype "passive"))
    )
    (net (code "56") (name "GND") (class "Default")
      (node (ref "*1") (pin "2") (pinfunction "GND_2") (pintype "passive"))
      (node (ref "*1") (pin "4") (pinfunction "VDD_4") (pintype "passive"))
      (node (ref "C1") (pin "2") (pinfunction "2_2") (pintype "passive"))
      (node (ref "C10") (pin "1") (pinfunction "1_1") (pintype "passive"))
      (node (ref "C11") (pin "1") (pinfunction "1_1") (pintype "passive"))
      (node (ref "C12") (pin "1") (pinfunction "1_1") (pintype "passive"))
      (node (ref "C13") (pin "1") (pinfunction "1_1") (pintype "passive"))
      (node (ref "C14") (pin "2") (pinfunction "2_2") (pintype "passive"))
      (node (ref "C15") (pin "2") (pinfunction "2_2") (pintype "passive"))
      (node (ref "C16") (pin "2") (pinfunction "2_2") (pintype "passive"))
      (node (ref "C17") (pin "1") (pinfunction "1_1") (pintype "passive"))
      (node (ref "C18") (pin "2") (pinfunction "2_2") (pintype "passive"))
      (node (ref "C19") (pin "1") (pinfunction "1_1") (pintype "passive"))
      (node (ref "C2") (pin "1") (pinfunction "1_1") (pintype "passive"))
      (node (ref "C20") (pin "1") (pinfunction "1_1") (pintype "passive"))
      (node (ref "C21") (pin "1") (pinfunction "1_1") (pintype "passive"))
      (node (ref "C22") (pin "2") (pinfunction "2_2") (pintype "passive"))
      (node (ref "C3") (pin "1") (pinfunction "1_1") (pintype "passive"))
      (node (ref "C4") (pin "1") (pinfunction "1_1") (pintype "passive"))
      (node (ref "C5") (pin "1") (pinfunction "1_1") (pintype "passive"))
      (node (ref "C6") (pin "1") (pinfunction "1_1") (pintype "passive"))
      (node (ref "C7") (pin "1") (pinfunction "1_1") (pintype "passive"))
      (node (ref "C8") (pin "1") (pinfunction "1_1") (pintype "passive"))
      (node (ref "C9") (pin "1") (pinfunction "1_1") (pintype "passive"))
      (node (ref "D1") (pin "2") (pinfunction "K_2") (pintype "passive"))
      (node (ref "J1") (pin "4") (pinfunction "VSS_4") (pintype "passive"))
      (node (ref "P1") (pin "4") (pinfunction "4_4") (pintype "passive"))
      (node (ref "P2") (pin "3") (pinfunction "3_3") (pintype "passive"))
      (node (ref "P3") (pin "3") (pinfunction "3_3") (pintype "passive"))
      (node (ref "P4") (pin "4") (pinfunction "4_4") (pintype "passive"))
      (node (ref "P5") (pin "4") (pinfunction "4_4") (pintype "passive"))
      (node (ref "P6") (pin "3") (pinfunction "3_3") (pintype "passive"))
      (node (ref "R21") (pin "1") (pinfunction "1_1") (pintype "passive"))
      (node (ref "R3") (pin "2") (pinfunction "2_2") (pintype "passive"))
      (node (ref "S1") (pin "2") (pinfunction "2_2") (pintype "passive"))
      (node (ref "S2") (pin "3") (pinfunction "B2_3") (pintype "passive"))
      (node (ref "S2") (pin "4") (pinfunction "B1_4") (pintype "passive"))
      (node (ref "U1") (pin "1") (pinfunction "GND_1") (pintype "passive"))
      (node (ref "U10") (pin "8") (pinfunction "GND_8") (pintype "passive"))
      (node (ref "U2") (pin "11") (pinfunction "GND_11") (pintype "passive"))
      (node (ref "U2") (pin "32") (pinfunction "GND_32") (pintype "passive"))
      (node (ref "U2") (pin "62") (pinfunction "GND_62") (pintype "passive"))
      (node (ref "U2") (pin "81") (pinfunction "GND_81") (pintype "passive"))
      (node (ref "U2") (pin "99") (pinfunction "GND_99") (pintype "passive"))
      (node (ref "U3") (pin "12") (pinfunction "GND_12") (pintype "passive"))
      (node (ref "U3") (pin "13") (pinfunction "GND_13") (pintype "passive"))
      (node (ref "U3") (pin "16") (pinfunction "GND_16") (pintype "passive"))
      (node (ref "U4") (pin "2") (pinfunction "GND_2") (pintype "passive"))
      (node (ref "U5") (pin "13") (pinfunction "GND_13") (pintype "passive"))
      (node (ref "U5") (pin "22") (pinfunction "GND_22") (pintype "passive"))
      (node (ref "U6") (pin "10") (pinfunction "3O_10") (pintype "passive"))
      (node (ref "U6") (pin "12") (pinfunction "4A_12") (pintype "passive"))
      (node (ref "U6") (pin "13") (pinfunction "4O_13") (pintype "passive"))
      (node (ref "U6") (pin "4") (pinfunction "2O_4") (pintype "passive"))
      (node (ref "U6") (pin "7") (pinfunction "GND_7") (pintype "passive"))
      (node (ref "U6") (pin "9") (pinfunction "3A_9") (pintype "passive"))
      (node (ref "U7") (pin "19") (pinfunction "GND_19") (pintype "passive"))
      (node (ref "U7") (pin "3") (pinfunction "GND_3") (pintype "passive"))
      (node (ref "U8") (pin "1") (pinfunction "1O_1") (pintype "passive"))
      (node (ref "U8") (pin "10") (pinfunction "3O_10") (pintype "passive"))
      (node (ref "U8") (pin "13") (pinfunction "4O_13") (pintype "passive"))
      (node (ref "U8") (pin "4") (pinfunction "2O_4") (pintype "passive"))
      (node (ref "U8") (pin "7") (pinfunction "GND_7") (pintype "passive"))
      (node (ref "U9") (pin "18") (pinfunction "GND_18") (pintype "passive"))
      (node (ref "USB1") (pin "5") (pinfunction "GND_5") (pintype "passive"))
      (node (ref "X1") (pin "2") (pinfunction "GND_2") (pintype "passive"))
      (node (ref "Y1") (pin "2") (pinfunction "2_2") (pintype "passive"))
    )
    (net (code "57") (name "Net-(*1-NC)") (class "Default")
      (node (ref "*1") (pin "1") (pinfunction "NC_1") (pintype "passive"))
      (node (ref "C22") (pin "1") (pinfunction "1_1") (pintype "passive"))
      (node (ref "U7") (pin "24") (pinfunction "XI_24") (pintype "passive"))
    )
    (net (code "58") (name "Net-(*1-OUT)") (class "Default")
      (node (ref "*1") (pin "3") (pinfunction "OUT_3") (pintype "passive"))
      (node (ref "C19") (pin "2") (pinfunction "2_2") (pintype "passive"))
      (node (ref "U7") (pin "25") (pinfunction "XO_25") (pintype "passive"))
    )
    (net (code "59") (name "Net-(D1-A)") (class "Default")
      (node (ref "D1") (pin "1") (pinfunction "A_1") (pintype "passive"))
      (node (ref "R1") (pin "2") (pinfunction "2_2") (pintype "passive"))
    )
    (net (code "60") (name "Net-(D2-A)") (class "Default")
      (node (ref "D2") (pin "1") (pinfunction "A_1") (pintype "passive"))
      (node (ref "L1") (pin "2") (pinfunction "2_2") (pintype "passive"))
      (node (ref "U4") (pin "1") (pinfunction "SW_1") (pintype "passive"))
    )
    (net (code "61") (name "Net-(D3-A)") (class "Default")
      (node (ref "D3") (pin "1") (pinfunction "A_1") (pintype "passive"))
      (node (ref "R4") (pin "2") (pinfunction "2_2") (pintype "passive"))
    )
    (net (code "62") (name "Net-(D4-A)") (class "Default")
      (node (ref "D4") (pin "1") (pinfunction "A_1") (pintype "passive"))
      (node (ref "R5") (pin "2") (pinfunction "2_2") (pintype "passive"))
    )
    (net (code "63") (name "Net-(J1-D+)") (class "Default")
      (node (ref "J1") (pin "3") (pinfunction "D+_3") (pintype "passive"))
      (node (ref "R16") (pin "1") (pinfunction "1_1") (pintype "passive"))
    )
    (net (code "64") (name "Net-(J1-D-)") (class "Default")
      (node (ref "J1") (pin "2") (pinfunction "D-_2") (pintype "passive"))
      (node (ref "R19") (pin "1") (pinfunction "1_1") (pintype "passive"))
    )
    (net (code "65") (name "Net-(U2-A1)") (class "Default")
      (node (ref "R6") (pin "1") (pinfunction "1_1") (pintype "passive"))
      (node (ref "U2") (pin "96") (pinfunction "A1_96") (pintype "passive"))
    )
    (net (code "66") (name "Net-(U2-A_ref)") (class "Default")
      (node (ref "C12") (pin "2") (pinfunction "2_2") (pintype "passive"))
      (node (ref "U2") (pin "98") (pinfunction "A_ref_98") (pintype "passive"))
    )
    (net (code "67") (name "Net-(U2-XTAL1)") (class "Default")
      (node (ref "U2") (pin "34") (pinfunction "XTAL1_34") (pintype "passive"))
      (node (ref "Y1") (pin "1") (pinfunction "1_1") (pintype "passive"))
    )
    (net (code "68") (name "Net-(U2-XTAL2)") (class "Default")
      (node (ref "U2") (pin "33") (pinfunction "XTAL2_33") (pintype "passive"))
      (node (ref "Y1") (pin "3") (pinfunction "3_3") (pintype "passive"))
    )
    (net (code "69") (name "Net-(U4-FB)") (class "Default")
      (node (ref "R2") (pin "2") (pinfunction "2_2") (pintype "passive"))
      (node (ref "R3") (pin "1") (pinfunction "1_1") (pintype "passive"))
      (node (ref "U4") (pin "3") (pinfunction "FB_3") (pintype "passive"))
    )
    (net (code "70") (name "Net-(U5-UART_RX)") (class "Default")
      (node (ref "R8") (pin "2") (pinfunction "2_2") (pintype "passive"))
      (node (ref "U5") (pin "2") (pinfunction "UART_RX_2") (pintype "passive"))
    )
    (net (code "71") (name "Net-(U5-UART_TX)") (class "Default")
      (node (ref "R7") (pin "2") (pinfunction "2_2") (pintype "passive"))
      (node (ref "U5") (pin "1") (pinfunction "UART_TX_1") (pintype "passive"))
    )
    (net (code "72") (name "Net-(U6-2Y)") (class "Default")
      (node (ref "R14") (pin "1") (pinfunction "1_1") (pintype "passive"))
      (node (ref "U6") (pin "6") (pinfunction "2Y_6") (pintype "passive"))
    )
    (net (code "73") (name "Net-(U7-D+)") (class "Default")
      (node (ref "R16") (pin "2") (pinfunction "2_2") (pintype "passive"))
      (node (ref "U7") (pin "21") (pinfunction "D+_21") (pintype "passive"))
    )
    (net (code "74") (name "Net-(U7-D-)") (class "Default")
      (node (ref "R19") (pin "2") (pinfunction "2_2") (pintype "passive"))
      (node (ref "U7") (pin "20") (pinfunction "D-_20") (pintype "passive"))
    )
    (net (code "75") (name "Net-(U7-INT)") (class "Default")
      (node (ref "R13") (pin "1") (pinfunction "1_1") (pintype "passive"))
      (node (ref "U7") (pin "18") (pinfunction "INT_18") (pintype "passive"))
    )
    (net (code "76") (name "Net-(U8-2A)") (class "Default")
      (node (ref "R20") (pin "2") (pinfunction "2_2") (pintype "passive"))
      (node (ref "U8") (pin "5") (pinfunction "2A_5") (pintype "passive"))
    )
    (net (code "77") (name "Net-(U9-STBY)") (class "Default")
      (node (ref "C21") (pin "2") (pinfunction "2_2") (pintype "passive"))
      (node (ref "R17") (pin "1") (pinfunction "1_1") (pintype "passive"))
      (node (ref "R18") (pin "1") (pinfunction "1_1") (pintype "passive"))
      (node (ref "U9") (pin "19") (pinfunction "STBY_19") (pintype "passive"))
      (node (ref "U9") (pin "20") (pinfunction "VCC_20") (pintype "passive"))
    )
    (net (code "78") (name "Net-(U10-V3)") (class "Default")
      (node (ref "C20") (pin "2") (pinfunction "2_2") (pintype "passive"))
      (node (ref "U10") (pin "5") (pinfunction "V3_5") (pintype "passive"))
    )
    (net (code "79") (name "PGND") (class "Default")
      (node (ref "C23") (pin "2") (pinfunction "2_2") (pintype "passive"))
      (node (ref "C24") (pin "1") (pinfunction "1_1") (pintype "passive"))
      (node (ref "R21") (pin "2") (pinfunction "2_2") (pintype "passive"))
      (node (ref "U9") (pin "10") (pinfunction "PGND2_10") (pintype "passive"))
      (node (ref "U9") (pin "3") (pinfunction "PGND1_3") (pintype "passive"))
      (node (ref "U9") (pin "4") (pinfunction "PGND1_4") (pintype "passive"))
      (node (ref "U9") (pin "9") (pinfunction "PGND2_9") (pintype "passive"))
    )
    (net (code "80") (name "VBAT") (class "Default")
      (node (ref "C6") (pin "2") (pinfunction "2_2") (pintype "passive"))
      (node (ref "C7") (pin "2") (pinfunction "2_2") (pintype "passive"))
      (node (ref "L1") (pin "1") (pinfunction "1_1") (pintype "passive"))
      (node (ref "P1") (pin "3") (pinfunction "3_3") (pintype "passive"))
      (node (ref "R1") (pin "1") (pinfunction "1_1") (pintype "passive"))
      (node (ref "R18") (pin "2") (pinfunction "2_2") (pintype "passive"))
      (node (ref "R6") (pin "2") (pinfunction "2_2") (pintype "passive"))
      (node (ref "U1") (pin "3") (pinfunction "Vin_3") (pintype "passive"))
      (node (ref "U4") (pin "4") (pinfunction "EN_4") (pintype "passive"))
      (node (ref "U4") (pin "5") (pinfunction "IN_5") (pintype "passive"))
    )
    (net (code "81") (name "Vin+") (class "Default")
      (node (ref "P1") (pin "1") (pinfunction "1_1") (pintype "passive"))
      (node (ref "P1") (pin "2") (pinfunction "2_2") (pintype "passive"))
      (node (ref "USB1") (pin "1") (pinfunction "VU+_1") (pintype "passive"))
    )
    (net (code "82") (name "unconnected-(J1-SHELL-Pad5)") (class "Default")
      (node (ref "J1") (pin "5") (pinfunction "SHELL_5") (pintype "passive"))
    )
    (net (code "83") (name "unconnected-(J1-SHELL-Pad6)") (class "Default")
      (node (ref "J1") (pin "6") (pinfunction "SHELL_6") (pintype "passive"))
    )
    (net (code "84") (name "unconnected-(U2-(PD4)-Pad47)") (class "Default")
      (node (ref "U2") (pin "47") (pinfunction "(PD4)_47") (pintype "passive"))
    )
    (net (code "85") (name "unconnected-(U2-(PD5)-Pad48)") (class "Default")
      (node (ref "U2") (pin "48") (pinfunction "(PD5)_48") (pintype "passive"))
    )
    (net (code "86") (name "unconnected-(U2-(PD6)-Pad49)") (class "Default")
      (node (ref "U2") (pin "49") (pinfunction "(PD6)_49") (pintype "passive"))
    )
    (net (code "87") (name "unconnected-(U2-(PE3)-Pad4)") (class "Default")
      (node (ref "U2") (pin "4") (pinfunction "(PE3)_4") (pintype "passive"))
    )
    (net (code "88") (name "unconnected-(U2-(PE6)-Pad8)") (class "Default")
      (node (ref "U2") (pin "8") (pinfunction "(PE6)_8") (pintype "passive"))
    )
    (net (code "89") (name "unconnected-(U2-(PE7)-Pad9)") (class "Default")
      (node (ref "U2") (pin "9") (pinfunction "(PE7)_9") (pintype "passive"))
    )
    (net (code "90") (name "unconnected-(U2-(PG3)-Pad28)") (class "Default")
      (node (ref "U2") (pin "28") (pinfunction "(PG3)_28") (pintype "passive"))
    )
    (net (code "91") (name "unconnected-(U2-(PG4)-Pad29)") (class "Default")
      (node (ref "U2") (pin "29") (pinfunction "(PG4)_29") (pintype "passive"))
    )
    (net (code "92") (name "unconnected-(U2-(PH2)-Pad14)") (class "Default")
      (node (ref "U2") (pin "14") (pinfunction "(PH2)_14") (pintype "passive"))
    )
    (net (code "93") (name "unconnected-(U2-(PH7)-Pad27)") (class "Default")
      (node (ref "U2") (pin "27") (pinfunction "(PH7)_27") (pintype "passive"))
    )
    (net (code "94") (name "unconnected-(U2-(PJ5)-Pad68)") (class "Default")
      (node (ref "U2") (pin "68") (pinfunction "(PJ5)_68") (pintype "passive"))
    )
    (net (code "95") (name "unconnected-(U2-(PJ6)-Pad69)") (class "Default")
      (node (ref "U2") (pin "69") (pinfunction "(PJ6)_69") (pintype "passive"))
    )
    (net (code "96") (name "unconnected-(U2-(PJ7)-Pad79)") (class "Default")
      (node (ref "U2") (pin "79") (pinfunction "(PJ7)_79") (pintype "passive"))
    )
    (net (code "97") (name "unconnected-(U2-A0-Pad97)") (class "Default")
      (node (ref "U2") (pin "97") (pinfunction "A0_97") (pintype "passive"))
    )
    (net (code "98") (name "unconnected-(U2-A2-Pad95)") (class "Default")
      (node (ref "U2") (pin "95") (pinfunction "A2_95") (pintype "passive"))
    )
    (net (code "99") (name "unconnected-(U2-A5-Pad92)") (class "Default")
      (node (ref "U2") (pin "92") (pinfunction "A5_92") (pintype "passive"))
    )
    (net (code "100") (name "unconnected-(U2-A6-Pad91)") (class "Default")
      (node (ref "U2") (pin "91") (pinfunction "A6_91") (pintype "passive"))
    )
    (net (code "101") (name "unconnected-(U2-A7-Pad90)") (class "Default")
      (node (ref "U2") (pin "90") (pinfunction "A7_90") (pintype "passive"))
    )
    (net (code "102") (name "unconnected-(U2-A8-Pad89)") (class "Default")
      (node (ref "U2") (pin "89") (pinfunction "A8_89") (pintype "passive"))
    )
    (net (code "103") (name "unconnected-(U2-A9-Pad88)") (class "Default")
      (node (ref "U2") (pin "88") (pinfunction "A9_88") (pintype "passive"))
    )
    (net (code "104") (name "unconnected-(U2-A10-Pad87)") (class "Default")
      (node (ref "U2") (pin "87") (pinfunction "A10_87") (pintype "passive"))
    )
    (net (code "105") (name "unconnected-(U2-A11-Pad86)") (class "Default")
      (node (ref "U2") (pin "86") (pinfunction "A11_86") (pintype "passive"))
    )
    (net (code "106") (name "unconnected-(U2-A12-Pad85)") (class "Default")
      (node (ref "U2") (pin "85") (pinfunction "A12_85") (pintype "passive"))
    )
    (net (code "107") (name "unconnected-(U2-A13-Pad84)") (class "Default")
      (node (ref "U2") (pin "84") (pinfunction "A13_84") (pintype "passive"))
    )
    (net (code "108") (name "unconnected-(U2-A14-Pad83)") (class "Default")
      (node (ref "U2") (pin "83") (pinfunction "A14_83") (pintype "passive"))
    )
    (net (code "109") (name "unconnected-(U2-A15-Pad82)") (class "Default")
      (node (ref "U2") (pin "82") (pinfunction "A15_82") (pintype "passive"))
    )
    (net (code "110") (name "unconnected-(U2-D2-Pad6)") (class "Default")
      (node (ref "U2") (pin "6") (pinfunction "D2_6") (pintype "passive"))
    )
    (net (code "111") (name "unconnected-(U2-D3-Pad7)") (class "Default")
      (node (ref "U2") (pin "7") (pinfunction "D3_7") (pintype "passive"))
    )
    (net (code "112") (name "unconnected-(U2-D4-Pad1)") (class "Default")
      (node (ref "U2") (pin "1") (pinfunction "D4_1") (pintype "passive"))
    )
    (net (code "113") (name "unconnected-(U2-D5-Pad5)") (class "Default")
      (node (ref "U2") (pin "5") (pinfunction "D5_5") (pintype "passive"))
    )
    (net (code "114") (name "unconnected-(U2-D6-Pad15)") (class "Default")
      (node (ref "U2") (pin "15") (pinfunction "D6_15") (pintype "passive"))
    )
    (net (code "115") (name "unconnected-(U2-D7-Pad16)") (class "Default")
      (node (ref "U2") (pin "16") (pinfunction "D7_16") (pintype "passive"))
    )
    (net (code "116") (name "unconnected-(U2-D8-Pad17)") (class "Default")
      (node (ref "U2") (pin "17") (pinfunction "D8_17") (pintype "passive"))
    )
    (net (code "117") (name "unconnected-(U2-D22-Pad78)") (class "Default")
      (node (ref "U2") (pin "78") (pinfunction "D22_78") (pintype "passive"))
    )
    (net (code "118") (name "unconnected-(U2-D23-Pad77)") (class "Default")
      (node (ref "U2") (pin "77") (pinfunction "D23_77") (pintype "passive"))
    )
    (net (code "119") (name "unconnected-(U2-D24-Pad76)") (class "Default")
      (node (ref "U2") (pin "76") (pinfunction "D24_76") (pintype "passive"))
    )
    (net (code "120") (name "unconnected-(U2-D25-Pad75)") (class "Default")
      (node (ref "U2") (pin "75") (pinfunction "D25_75") (pintype "passive"))
    )
    (net (code "121") (name "unconnected-(U2-D30-Pad60)") (class "Default")
      (node (ref "U2") (pin "60") (pinfunction "D30_60") (pintype "passive"))
    )
    (net (code "122") (name "unconnected-(U2-D31-Pad59)") (class "Default")
      (node (ref "U2") (pin "59") (pinfunction "D31_59") (pintype "passive"))
    )
    (net (code "123") (name "unconnected-(U2-D38-Pad50)") (class "Default")
      (node (ref "U2") (pin "50") (pinfunction "D38_50") (pintype "passive"))
    )
    (net (code "124") (name "unconnected-(U2-D39-Pad70)") (class "Default")
      (node (ref "U2") (pin "70") (pinfunction "D39_70") (pintype "passive"))
    )
    (net (code "125") (name "unconnected-(U2-D44-Pad40)") (class "Default")
      (node (ref "U2") (pin "40") (pinfunction "D44_40") (pintype "passive"))
    )
    (net (code "126") (name "unconnected-(U2-D45-Pad39)") (class "Default")
      (node (ref "U2") (pin "39") (pinfunction "D45_39") (pintype "passive"))
    )
    (net (code "127") (name "unconnected-(U2-D46-Pad38)") (class "Default")
      (node (ref "U2") (pin "38") (pinfunction "D46_38") (pintype "passive"))
    )
    (net (code "128") (name "unconnected-(U2-D47-Pad37)") (class "Default")
      (node (ref "U2") (pin "37") (pinfunction "D47_37") (pintype "passive"))
    )
    (net (code "129") (name "unconnected-(U2-D48-Pad36)") (class "Default")
      (node (ref "U2") (pin "36") (pinfunction "D48_36") (pintype "passive"))
    )
    (net (code "130") (name "unconnected-(U2-D49-Pad35)") (class "Default")
      (node (ref "U2") (pin "35") (pinfunction "D49_35") (pintype "passive"))
    )
    (net (code "131") (name "unconnected-(U2-D53-Pad19)") (class "Default")
      (node (ref "U2") (pin "19") (pinfunction "D53_19") (pintype "passive"))
    )
    (net (code "132") (name "unconnected-(U3-INT2-Pad9)") (class "Default")
      (node (ref "U3") (pin "9") (pinfunction "INT2_9") (pintype "passive"))
    )
    (net (code "133") (name "unconnected-(U3-NC-Pad2)") (class "Default")
      (node (ref "U3") (pin "2") (pinfunction "NC_2") (pintype "passive+no_connect"))
    )
    (net (code "134") (name "unconnected-(U3-NC-Pad15)") (class "Default")
      (node (ref "U3") (pin "15") (pinfunction "NC_15") (pintype "passive+no_connect"))
    )
    (net (code "135") (name "unconnected-(U3-RESERVED-Pad3)") (class "Default")
      (node (ref "U3") (pin "3") (pinfunction "RESERVED_3") (pintype "passive+no_connect"))
    )
    (net (code "136") (name "unconnected-(U3-RESERVED-Pad5)") (class "Default")
      (node (ref "U3") (pin "5") (pinfunction "RESERVED_5") (pintype "passive+no_connect"))
    )
    (net (code "137") (name "unconnected-(U3-RESERVED-Pad10)") (class "Default")
      (node (ref "U3") (pin "10") (pinfunction "RESERVED_10") (pintype "passive+no_connect"))
    )
    (net (code "138") (name "unconnected-(U4-NC-Pad6)") (class "Default")
      (node (ref "U4") (pin "6") (pinfunction "NC_6") (pintype "passive"))
    )
    (net (code "139") (name "unconnected-(U5-AIO0-Pad9)") (class "Default")
      (node (ref "U5") (pin "9") (pinfunction "AIO0_9") (pintype "passive"))
    )
    (net (code "140") (name "unconnected-(U5-AIO1-Pad10)") (class "Default")
      (node (ref "U5") (pin "10") (pinfunction "AIO1_10") (pintype "passive"))
    )
    (net (code "141") (name "unconnected-(U5-GND-Pad14)") (class "Default")
      (node (ref "U5") (pin "14") (pinfunction "GND_14") (pintype "passive"))
    )
    (net (code "142") (name "unconnected-(U5-GND-Pad21)") (class "Default")
      (node (ref "U5") (pin "21") (pinfunction "GND_21") (pintype "passive"))
    )
    (net (code "143") (name "unconnected-(U5-PCM_CLK-Pad5)") (class "Default")
      (node (ref "U5") (pin "5") (pinfunction "PCM_CLK_5") (pintype "passive"))
    )
    (net (code "144") (name "unconnected-(U5-PCM_IN-Pad7)") (class "Default")
      (node (ref "U5") (pin "7") (pinfunction "PCM_IN_7") (pintype "passive"))
    )
    (net (code "145") (name "unconnected-(U5-PCM_OUT-Pad6)") (class "Default")
      (node (ref "U5") (pin "6") (pinfunction "PCM_OUT_6") (pintype "passive"))
    )
    (net (code "146") (name "unconnected-(U5-PCM_SYNC-Pad8)") (class "Default")
      (node (ref "U5") (pin "8") (pinfunction "PCM_SYNC_8") (pintype "passive"))
    )
    (net (code "147") (name "unconnected-(U5-PIO0-Pad23)") (class "Default")
      (node (ref "U5") (pin "23") (pinfunction "PIO0_23") (pintype "passive"))
    )
    (net (code "148") (name "unconnected-(U5-PIO1-Pad24)") (class "Default")
      (node (ref "U5") (pin "24") (pinfunction "PIO1_24") (pintype "passive"))
    )
    (net (code "149") (name "unconnected-(U5-PIO2-Pad25)") (class "Default")
      (node (ref "U5") (pin "25") (pinfunction "PIO2_25") (pintype "passive"))
    )
    (net (code "150") (name "unconnected-(U5-PIO3-Pad26)") (class "Default")
      (node (ref "U5") (pin "26") (pinfunction "PIO3_26") (pintype "passive"))
    )
    (net (code "151") (name "unconnected-(U5-PIO4-Pad27)") (class "Default")
      (node (ref "U5") (pin "27") (pinfunction "PIO4_27") (pintype "passive"))
    )
    (net (code "152") (name "unconnected-(U5-PIO5-Pad28)") (class "Default")
      (node (ref "U5") (pin "28") (pinfunction "PIO5_28") (pintype "passive"))
    )
    (net (code "153") (name "unconnected-(U5-PIO6-Pad29)") (class "Default")
      (node (ref "U5") (pin "29") (pinfunction "PIO6_29") (pintype "passive"))
    )
    (net (code "154") (name "unconnected-(U5-PIO7-Pad30)") (class "Default")
      (node (ref "U5") (pin "30") (pinfunction "PIO7_30") (pintype "passive"))
    )
    (net (code "155") (name "unconnected-(U5-PIO8-Pad31)") (class "Default")
      (node (ref "U5") (pin "31") (pinfunction "PIO8_31") (pintype "passive"))
    )
    (net (code "156") (name "unconnected-(U5-PIO10-Pad33)") (class "Default")
      (node (ref "U5") (pin "33") (pinfunction "PIO10_33") (pintype "passive"))
    )
    (net (code "157") (name "unconnected-(U5-RESETB-Pad11)") (class "Default")
      (node (ref "U5") (pin "11") (pinfunction "RESETB_11") (pintype "passive"))
    )
    (net (code "158") (name "unconnected-(U5-SPI_CLK-Pad19)") (class "Default")
      (node (ref "U5") (pin "19") (pinfunction "SPI_CLK_19") (pintype "passive"))
    )
    (net (code "159") (name "unconnected-(U5-SPI_CSB-Pad16)") (class "Default")
      (node (ref "U5") (pin "16") (pinfunction "SPI_CSB_16") (pintype "passive"))
    )
    (net (code "160") (name "unconnected-(U5-SPI_MISO-Pad18)") (class "Default")
      (node (ref "U5") (pin "18") (pinfunction "SPI_MISO_18") (pintype "passive"))
    )
    (net (code "161") (name "unconnected-(U5-SPI_MOSI-Pad17)") (class "Default")
      (node (ref "U5") (pin "17") (pinfunction "SPI_MOSI_17") (pintype "passive"))
    )
    (net (code "162") (name "unconnected-(U5-UART_CTS-Pad3)") (class "Default")
      (node (ref "U5") (pin "3") (pinfunction "UART_CTS_3") (pintype "passive"))
    )
    (net (code "163") (name "unconnected-(U5-UART_RTS-Pad4)") (class "Default")
      (node (ref "U5") (pin "4") (pinfunction "UART_RTS_4") (pintype "passive"))
    )
    (net (code "164") (name "unconnected-(U5-USB_D--Pad15)") (class "Default")
      (node (ref "U5") (pin "15") (pinfunction "USB_D-_15") (pintype "passive"))
    )
    (net (code "165") (name "unconnected-(U5-USB_D--Pad20)") (class "Default")
      (node (ref "U5") (pin "20") (pinfunction "USB_D-_20") (pintype "passive"))
    )
    (net (code "166") (name "unconnected-(U6-2A-Pad5)") (class "Default")
      (node (ref "U6") (pin "5") (pinfunction "2A_5") (pintype "passive"))
    )
    (net (code "167") (name "unconnected-(U6-3Y-Pad8)") (class "Default")
      (node (ref "U6") (pin "8") (pinfunction "3Y_8") (pintype "passive"))
    )
    (net (code "168") (name "unconnected-(U6-4Y-Pad11)") (class "Default")
      (node (ref "U6") (pin "11") (pinfunction "4Y_11") (pintype "passive"))
    )
    (net (code "169") (name "unconnected-(U7-GPIN0-Pad26)") (class "Default")
      (node (ref "U7") (pin "26") (pinfunction "GPIN0_26") (pintype "passive"))
    )
    (net (code "170") (name "unconnected-(U7-GPIN1-Pad27)") (class "Default")
      (node (ref "U7") (pin "27") (pinfunction "GPIN1_27") (pintype "passive"))
    )
    (net (code "171") (name "unconnected-(U7-GPIN2-Pad28)") (class "Default")
      (node (ref "U7") (pin "28") (pinfunction "GPIN2_28") (pintype "passive"))
    )
    (net (code "172") (name "unconnected-(U7-GPIN3-Pad29)") (class "Default")
      (node (ref "U7") (pin "29") (pinfunction "GPIN3_29") (pintype "passive"))
    )
    (net (code "173") (name "unconnected-(U7-GPIN4-Pad30)") (class "Default")
      (node (ref "U7") (pin "30") (pinfunction "GPIN4_30") (pintype "passive"))
    )
    (net (code "174") (name "unconnected-(U7-GPIN5-Pad31)") (class "Default")
      (node (ref "U7") (pin "31") (pinfunction "GPIN5_31") (pintype "passive"))
    )
    (net (code "175") (name "unconnected-(U7-GPIN6-Pad32)") (class "Default")
      (node (ref "U7") (pin "32") (pinfunction "GPIN6_32") (pintype "passive"))
    )
    (net (code "176") (name "unconnected-(U7-GPIN7-Pad1)") (class "Default")
      (node (ref "U7") (pin "1") (pinfunction "GPIN7_1") (pintype "passive"))
    )
    (net (code "177") (name "unconnected-(U7-GPOUT0-Pad4)") (class "Default")
      (node (ref "U7") (pin "4") (pinfunction "GPOUT0_4") (pintype "passive"))
    )
    (net (code "178") (name "unconnected-(U7-GPOUT1-Pad5)") (class "Default")
      (node (ref "U7") (pin "5") (pinfunction "GPOUT1_5") (pintype "passive"))
    )
    (net (code "179") (name "unconnected-(U7-GPOUT2-Pad6)") (class "Default")
      (node (ref "U7") (pin "6") (pinfunction "GPOUT2_6") (pintype "passive"))
    )
    (net (code "180") (name "unconnected-(U7-GPOUT3-Pad7)") (class "Default")
      (node (ref "U7") (pin "7") (pinfunction "GPOUT3_7") (pintype "passive"))
    )
    (net (code "181") (name "unconnected-(U7-GPOUT4-Pad8)") (class "Default")
      (node (ref "U7") (pin "8") (pinfunction "GPOUT4_8") (pintype "passive"))
    )
    (net (code "182") (name "unconnected-(U7-GPOUT5-Pad9)") (class "Default")
      (node (ref "U7") (pin "9") (pinfunction "GPOUT5_9") (pintype "passive"))
    )
    (net (code "183") (name "unconnected-(U7-GPOUT6-Pad10)") (class "Default")
      (node (ref "U7") (pin "10") (pinfunction "GPOUT6_10") (pintype "passive"))
    )
    (net (code "184") (name "unconnected-(U7-GPOUT7-Pad11)") (class "Default")
      (node (ref "U7") (pin "11") (pinfunction "GPOUT7_11") (pintype "passive"))
    )
    (net (code "185") (name "unconnected-(U7-GPX-Pad17)") (class "Default")
      (node (ref "U7") (pin "17") (pinfunction "GPX_17") (pintype "passive"))
    )
    (net (code "186") (name "unconnected-(U7-VBCOMP-Pad22)") (class "Default")
      (node (ref "U7") (pin "22") (pinfunction "VBCOMP_22") (pintype "passive"))
    )
    (net (code "187") (name "unconnected-(U10-ACT-Pad2)") (class "Default")
      (node (ref "U10") (pin "2") (pinfunction "ACT_2") (pintype "passive"))
    )
    (net (code "188") (name "unconnected-(U10-CKO-Pad1)") (class "Default")
      (node (ref "U10") (pin "1") (pinfunction "CKO_1") (pintype "passive"))
    )
    (net (code "189") (name "unconnected-(U10-CTS-Pad11)") (class "Default")
      (node (ref "U10") (pin "11") (pinfunction "CTS_11") (pintype "passive"))
    )
    (net (code "190") (name "unconnected-(U10-DCD-Pad14)") (class "Default")
      (node (ref "U10") (pin "14") (pinfunction "DCD_14") (pintype "passive"))
    )
    (net (code "191") (name "unconnected-(U10-DSR-Pad12)") (class "Default")
      (node (ref "U10") (pin "12") (pinfunction "DSR_12") (pintype "passive"))
    )
    (net (code "192") (name "unconnected-(U10-DTR-Pad15)") (class "Default")
      (node (ref "U10") (pin "15") (pinfunction "DTR_15") (pintype "passive"))
    )
    (net (code "193") (name "unconnected-(U10-NC-Pad17)") (class "Default")
      (node (ref "U10") (pin "17") (pinfunction "NC_17") (pintype "passive"))
    )
    (net (code "194") (name "unconnected-(U10-NOS-Pad20)") (class "Default")
      (node (ref "U10") (pin "20") (pinfunction "NOS_20") (pintype "passive"))
    )
    (net (code "195") (name "unconnected-(U10-RI-Pad13)") (class "Default")
      (node (ref "U10") (pin "13") (pinfunction "RI_13") (pintype "passive"))
    )
    (net (code "196") (name "unconnected-(U10-RS232-Pad18)") (class "Default")
      (node (ref "U10") (pin "18") (pinfunction "RS232_18") (pintype "passive"))
    )
    (net (code "197") (name "unconnected-(U10-RTS-Pad16)") (class "Default")
      (node (ref "U10") (pin "16") (pinfunction "RTS_16") (pintype "passive"))
    )
    (net (code "198") (name "unconnected-(U10-XO-Pad10)") (class "Default")
      (node (ref "U10") (pin "10") (pinfunction "XO_10") (pintype "passive"))
    )
    (net (code "199") (name "unconnected-(USB1-Pad4)") (class "Default")
      (node (ref "USB1") (pin "4") (pinfunction "4_4") (pintype "passive"))
    )
    (net (code "200") (name "unconnected-(X1-NC-Pad1)") (class "Default")
      (node (ref "X1") (pin "1") (pinfunction "NC_1") (pintype "passive"))
    )
  )
)
